# SwitchingRegulator.net
KiCad netlist of a schematic drawn in EAGLE
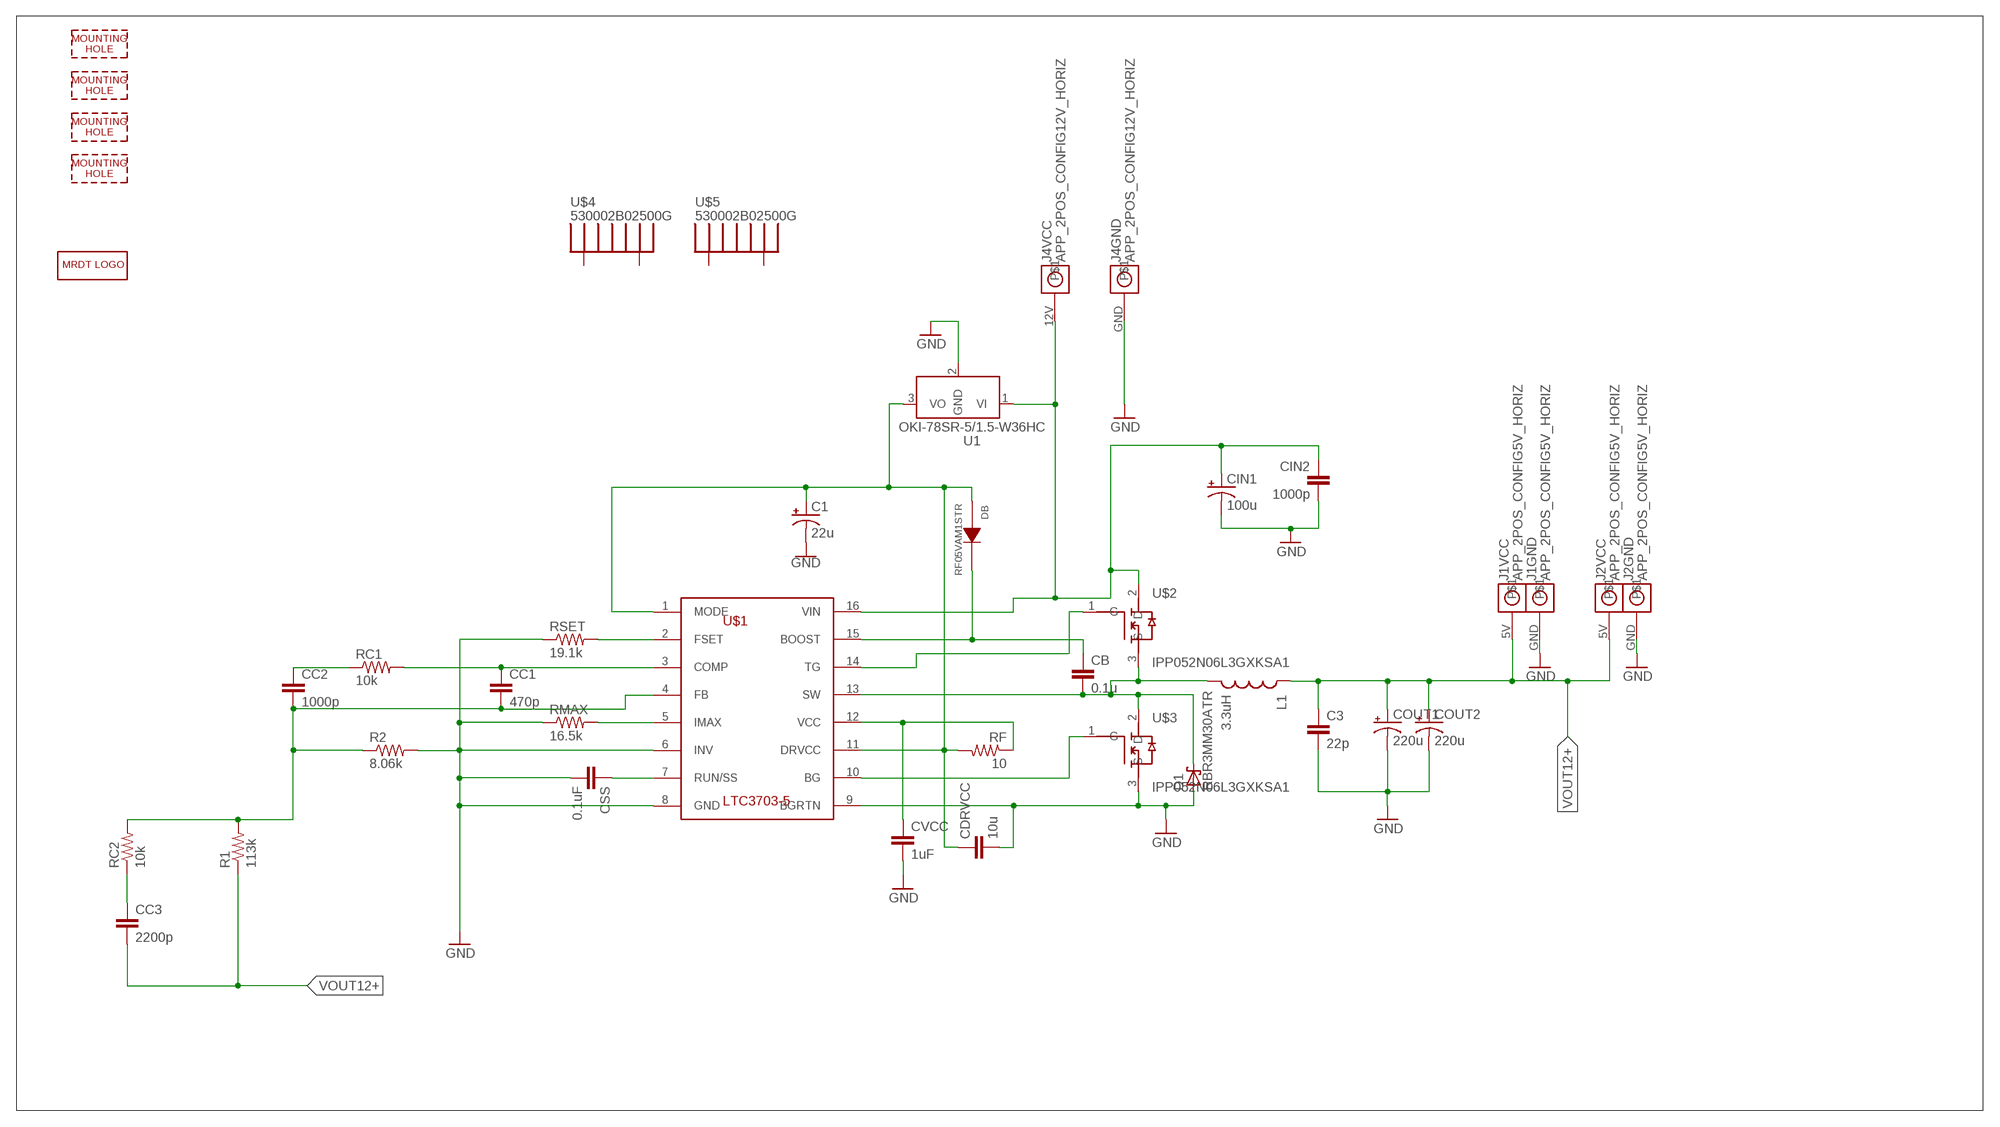
[diagram p0: schematic, sheet 1]

(export (version "E")
  (design (tool "Eeschema 10.0.6"))
  (components
    (comp (ref "C1")
      (value "22u")
      (footprint "eagle-import:CAP_POL_22UF")
      (libsource (lib "eagle-import") (part "UCZ1K220MCL1GS"))
    )
    (comp (ref "C3")
      (value "22p")
      (footprint "eagle-import:0603-CAP")
      (libsource (lib "eagle-import") (part "CAP0603-CAP"))
    )
    (comp (ref "CB")
      (value "0.1u")
      (footprint "eagle-import:0603-CAP")
      (libsource (lib "eagle-import") (part "CAP0603-CAP"))
    )
    (comp (ref "CC1")
      (value "470p")
      (footprint "eagle-import:0603-CAP")
      (libsource (lib "eagle-import") (part "CAP0603-CAP"))
    )
    (comp (ref "CC2")
      (value "1000p")
      (footprint "eagle-import:0603-CAP")
      (libsource (lib "eagle-import") (part "CAP0603-CAP"))
    )
    (comp (ref "CC3")
      (value "2200p")
      (footprint "eagle-import:0603-CAP")
      (libsource (lib "eagle-import") (part "CAP0603-CAP"))
    )
    (comp (ref "CDRVCC")
      (value "10u")
      (footprint "eagle-import:0603-CAP")
      (libsource (lib "eagle-import") (part "CAP0603-CAP"))
    )
    (comp (ref "CIN1")
      (value "100u")
      (footprint "eagle-import:CAP_POL_220UF")
      (libsource (lib "eagle-import") (part "B41858C9107M000"))
    )
    (comp (ref "CIN2")
      (value "1000p")
      (footprint "eagle-import:0603-CAP")
      (libsource (lib "eagle-import") (part "CAP0603-CAP"))
    )
    (comp (ref "COUT1")
      (value "220u")
      (footprint "eagle-import:CAP_POL_220UF")
      (libsource (lib "eagle-import") (part "EGPD101ELL221MK25H"))
    )
    (comp (ref "COUT2")
      (value "220u")
      (footprint "eagle-import:CAP_POL_220UF")
      (libsource (lib "eagle-import") (part "EGPD101ELL221MK25H"))
    )
    (comp (ref "CSS")
      (value "0.1uF")
      (footprint "eagle-import:0603-CAP")
      (libsource (lib "eagle-import") (part "CAP0603-CAP"))
    )
    (comp (ref "CVCC")
      (value "1uF")
      (footprint "eagle-import:0603-CAP")
      (libsource (lib "eagle-import") (part "CAP0603-CAP"))
    )
    (comp (ref "D1")
      (value "RBR3MM30ATR")
      (footprint "eagle-import:DIODE_SCHOTTKY_30V_1A")
      (libsource (lib "eagle-import") (part "RBR3MM30ATR"))
    )
    (comp (ref "DB")
      (value "RF05VAM1STR")
      (footprint "eagle-import:DIODE_STANDARD_100V")
      (libsource (lib "eagle-import") (part "RF05VAM1STR"))
    )
    (comp (ref "H1")
      (value "MOUNTING_HOLE#8")
      (footprint "eagle-import:#8_SCREW")
      (libsource (lib "eagle-import") (part "MOUNTING_HOLE#8"))
    )
    (comp (ref "H2")
      (value "MOUNTING_HOLE#8")
      (footprint "eagle-import:#8_SCREW")
      (libsource (lib "eagle-import") (part "MOUNTING_HOLE#8"))
    )
    (comp (ref "H3")
      (value "MOUNTING_HOLE#8")
      (footprint "eagle-import:#8_SCREW")
      (libsource (lib "eagle-import") (part "MOUNTING_HOLE#8"))
    )
    (comp (ref "H4")
      (value "MOUNTING_HOLE#8")
      (footprint "eagle-import:#8_SCREW")
      (libsource (lib "eagle-import") (part "MOUNTING_HOLE#8"))
    )
    (comp (ref "J1")
      (value "APP_2POS_CONFIG5V_HORIZ")
      (footprint "eagle-import:APP45_5V_HORIZ_CONFIG")
      (libsource (lib "eagle-import") (part "APP_2POS_CONFIG5V_HORIZ"))
    )
    (comp (ref "J2")
      (value "APP_2POS_CONFIG5V_HORIZ")
      (footprint "eagle-import:APP45_5V_HORIZ_CONFIG")
      (libsource (lib "eagle-import") (part "APP_2POS_CONFIG5V_HORIZ"))
    )
    (comp (ref "J4")
      (value "APP_2POS_CONFIG12V_HORIZ")
      (footprint "eagle-import:APP45_12V_HORIZ_CONFIG")
      (libsource (lib "eagle-import") (part "APP_2POS_CONFIG12V_HORIZ"))
    )
    (comp (ref "L1")
      (value "3.3uH")
      (footprint "eagle-import:PLANAR_INDUCTOR_3.3UH")
      (libsource (lib "eagle-import") (part "PQ3218-3R3-70-T"))
    )
    (comp (ref "LOGO1")
      (value "MRDT_LOGO")
      (footprint "eagle-import:MRDT_LOGO")
      (libsource (lib "eagle-import") (part "MRDT_LOGO"))
    )
    (comp (ref "R1")
      (value "113k")
      (footprint "eagle-import:0603-RES")
      (libsource (lib "eagle-import") (part "RESISTOR0603-RES"))
    )
    (comp (ref "R2")
      (value "8.06k")
      (footprint "eagle-import:0603-RES")
      (libsource (lib "eagle-import") (part "RESISTOR0603-RES"))
    )
    (comp (ref "RC1")
      (value "10k")
      (footprint "eagle-import:0603-RES")
      (libsource (lib "eagle-import") (part "RESISTOR0603-RES"))
    )
    (comp (ref "RC2")
      (value "10k")
      (footprint "eagle-import:0603-RES")
      (libsource (lib "eagle-import") (part "RESISTOR0603-RES"))
    )
    (comp (ref "RF")
      (value "10")
      (footprint "eagle-import:0603-RES")
      (libsource (lib "eagle-import") (part "RESISTOR0603-RES"))
    )
    (comp (ref "RMAX")
      (value "16.5k")
      (footprint "eagle-import:0603-RES")
      (libsource (lib "eagle-import") (part "RESISTOR0603-RES"))
    )
    (comp (ref "RSET")
      (value "19.1k")
      (footprint "eagle-import:0603-RES")
      (libsource (lib "eagle-import") (part "RESISTOR0603-RES"))
    )
    (comp (ref "U$1")
      (value "LTC3703-5")
      (footprint "eagle-import:SSOP-16")
      (libsource (lib "eagle-import") (part "LTC3703-5"))
    )
    (comp (ref "U$2")
      (value "IPP052N06L3GXKSA1")
      (footprint "eagle-import:TO-220")
      (libsource (lib "eagle-import") (part "IPP052N06L3GXKSA1"))
    )
    (comp (ref "U$3")
      (value "IPP052N06L3GXKSA1")
      (footprint "eagle-import:TO-220")
      (libsource (lib "eagle-import") (part "IPP052N06L3GXKSA1"))
    )
    (comp (ref "U$4")
      (value "530002B02500G")
      (footprint "eagle-import:RADIAL_FIN_HEATSINK")
      (libsource (lib "eagle-import") (part "530002B02500G"))
    )
    (comp (ref "U$5")
      (value "530002B02500G")
      (footprint "eagle-import:RADIAL_FIN_HEATSINK")
      (libsource (lib "eagle-import") (part "530002B02500G"))
    )
    (comp (ref "U1")
      (value "OKI-78SR-5/1.5-W36HC")
      (footprint "eagle-import:OKI-78SR_HORIZ")
      (libsource (lib "eagle-import") (part "OKI-78SR-/1.5-W36?CH5"))
    )
  )
  (nets
    (net (code "1") (name "GND") (class "Default")
      (node (ref "C1") (pin "-") (pinfunction "-_-") (pintype "passive"))
      (node (ref "C3") (pin "2") (pinfunction "2_2") (pintype "passive"))
      (node (ref "CDRVCC") (pin "2") (pinfunction "2_2") (pintype "passive"))
      (node (ref "CIN1") (pin "GND") (pinfunction "-_GND") (pintype "passive"))
      (node (ref "CIN2") (pin "2") (pinfunction "2_2") (pintype "passive"))
      (node (ref "COUT1") (pin "GND") (pinfunction "-_GND") (pintype "passive"))
      (node (ref "COUT2") (pin "GND") (pinfunction "-_GND") (pintype "passive"))
      (node (ref "CSS") (pin "2") (pinfunction "2_2") (pintype "passive"))
      (node (ref "CVCC") (pin "2") (pinfunction "2_2") (pintype "passive"))
      (node (ref "D1") (pin "P$1") (pinfunction "A_P$1") (pintype "passive"))
      (node (ref "J1") (pin "GND") (pinfunction "P$1_GND") (pintype "bidirectional"))
      (node (ref "J2") (pin "GND") (pinfunction "P$1_GND") (pintype "bidirectional"))
      (node (ref "J4") (pin "GND") (pinfunction "P$1_GND") (pintype "bidirectional"))
      (node (ref "R2") (pin "2") (pinfunction "2_2") (pintype "passive"))
      (node (ref "RMAX") (pin "1") (pinfunction "1_1") (pintype "passive"))
      (node (ref "RSET") (pin "1") (pinfunction "1_1") (pintype "passive"))
      (node (ref "U$1") (pin "6") (pinfunction "INV_6") (pintype "bidirectional"))
      (node (ref "U$1") (pin "8") (pinfunction "GND_8") (pintype "bidirectional"))
      (node (ref "U$1") (pin "9") (pinfunction "BGRTN_9") (pintype "bidirectional"))
      (node (ref "U$3") (pin "3") (pinfunction "S_3") (pintype "bidirectional"))
      (node (ref "U1") (pin "2") (pinfunction "GND_2") (pintype "bidirectional"))
    )
    (net (code "2") (name "Net-(CC2-Pad1)") (class "Default")
      (node (ref "CC2") (pin "1") (pinfunction "1_1") (pintype "passive"))
      (node (ref "RC1") (pin "1") (pinfunction "1_1") (pintype "passive"))
    )
    (net (code "3") (name "Net-(CC3-Pad1)") (class "Default")
      (node (ref "CC3") (pin "1") (pinfunction "1_1") (pintype "passive"))
      (node (ref "RC2") (pin "1") (pinfunction "1_1") (pintype "passive"))
    )
    (net (code "4") (name "Net-(D1-C)") (class "Default")
      (node (ref "CB") (pin "2") (pinfunction "2_2") (pintype "passive"))
      (node (ref "D1") (pin "P$2") (pinfunction "C_P$2") (pintype "passive"))
      (node (ref "L1") (pin "P$2") (pinfunction "2_P$2") (pintype "passive"))
      (node (ref "U$1") (pin "13") (pinfunction "SW_13") (pintype "bidirectional"))
      (node (ref "U$2") (pin "3") (pinfunction "S_3") (pintype "bidirectional"))
      (node (ref "U$3") (pin "2") (pinfunction "D_2") (pintype "bidirectional"))
    )
    (net (code "5") (name "Net-(DB-A)") (class "Default")
      (node (ref "C1") (pin "+") (pinfunction "+_+") (pintype "passive"))
      (node (ref "CDRVCC") (pin "1") (pinfunction "1_1") (pintype "passive"))
      (node (ref "DB") (pin "P$2") (pinfunction "A_P$2") (pintype "bidirectional"))
      (node (ref "RF") (pin "2") (pinfunction "2_2") (pintype "passive"))
      (node (ref "U$1") (pin "1") (pinfunction "MODE_1") (pintype "bidirectional"))
      (node (ref "U$1") (pin "11") (pinfunction "DRVCC_11") (pintype "bidirectional"))
      (node (ref "U1") (pin "3") (pinfunction "VO_3") (pintype "bidirectional"))
    )
    (net (code "6") (name "Net-(DB-K)") (class "Default")
      (node (ref "CB") (pin "1") (pinfunction "1_1") (pintype "passive"))
      (node (ref "DB") (pin "P$1") (pinfunction "K_P$1") (pintype "bidirectional"))
      (node (ref "U$1") (pin "15") (pinfunction "BOOST_15") (pintype "bidirectional"))
    )
    (net (code "7") (name "Net-(J4B-P$1)") (class "Default")
      (node (ref "CIN1") (pin "+") (pinfunction "+_+") (pintype "passive"))
      (node (ref "CIN2") (pin "1") (pinfunction "1_1") (pintype "passive"))
      (node (ref "J4") (pin "12V") (pinfunction "P$1_12V") (pintype "bidirectional"))
      (node (ref "U$1") (pin "16") (pinfunction "VIN_16") (pintype "bidirectional"))
      (node (ref "U$2") (pin "2") (pinfunction "D_2") (pintype "bidirectional"))
      (node (ref "U1") (pin "1") (pinfunction "VI_1") (pintype "bidirectional"))
    )
    (net (code "8") (name "Net-(U$1-BG)") (class "Default")
      (node (ref "U$1") (pin "10") (pinfunction "BG_10") (pintype "bidirectional"))
      (node (ref "U$3") (pin "1") (pinfunction "G_1") (pintype "bidirectional"))
    )
    (net (code "9") (name "Net-(U$1-COMP)") (class "Default")
      (node (ref "CC1") (pin "1") (pinfunction "1_1") (pintype "passive"))
      (node (ref "RC1") (pin "2") (pinfunction "2_2") (pintype "passive"))
      (node (ref "U$1") (pin "3") (pinfunction "COMP_3") (pintype "bidirectional"))
    )
    (net (code "10") (name "Net-(U$1-FB)") (class "Default")
      (node (ref "CC1") (pin "2") (pinfunction "2_2") (pintype "passive"))
      (node (ref "CC2") (pin "2") (pinfunction "2_2") (pintype "passive"))
      (node (ref "R1") (pin "2") (pinfunction "2_2") (pintype "passive"))
      (node (ref "R2") (pin "1") (pinfunction "1_1") (pintype "passive"))
      (node (ref "RC2") (pin "2") (pinfunction "2_2") (pintype "passive"))
      (node (ref "U$1") (pin "4") (pinfunction "FB_4") (pintype "bidirectional"))
    )
    (net (code "11") (name "Net-(U$1-FSET)") (class "Default")
      (node (ref "RSET") (pin "2") (pinfunction "2_2") (pintype "passive"))
      (node (ref "U$1") (pin "2") (pinfunction "FSET_2") (pintype "bidirectional"))
    )
    (net (code "12") (name "Net-(U$1-IMAX)") (class "Default")
      (node (ref "RMAX") (pin "2") (pinfunction "2_2") (pintype "passive"))
      (node (ref "U$1") (pin "5") (pinfunction "IMAX_5") (pintype "bidirectional"))
    )
    (net (code "13") (name "Net-(U$1-RUN{slash}SS)") (class "Default")
      (node (ref "CSS") (pin "1") (pinfunction "1_1") (pintype "passive"))
      (node (ref "U$1") (pin "7") (pinfunction "RUN/SS_7") (pintype "bidirectional"))
    )
    (net (code "14") (name "Net-(U$1-TG)") (class "Default")
      (node (ref "U$1") (pin "14") (pinfunction "TG_14") (pintype "bidirectional"))
      (node (ref "U$2") (pin "1") (pinfunction "G_1") (pintype "bidirectional"))
    )
    (net (code "15") (name "Net-(U$1-VCC)") (class "Default")
      (node (ref "CVCC") (pin "1") (pinfunction "1_1") (pintype "passive"))
      (node (ref "RF") (pin "1") (pinfunction "1_1") (pintype "passive"))
      (node (ref "U$1") (pin "12") (pinfunction "VCC_12") (pintype "bidirectional"))
    )
    (net (code "16") (name "VOUT12+") (class "Default")
      (node (ref "C3") (pin "1") (pinfunction "1_1") (pintype "passive"))
      (node (ref "CC3") (pin "2") (pinfunction "2_2") (pintype "passive"))
      (node (ref "COUT1") (pin "+") (pinfunction "+_+") (pintype "passive"))
      (node (ref "COUT2") (pin "+") (pinfunction "+_+") (pintype "passive"))
      (node (ref "J1") (pin "5V") (pinfunction "P$1_5V") (pintype "bidirectional"))
      (node (ref "J2") (pin "5V") (pinfunction "P$1_5V") (pintype "bidirectional"))
      (node (ref "L1") (pin "P$1") (pinfunction "1_P$1") (pintype "passive"))
      (node (ref "R1") (pin "1") (pinfunction "1_1") (pintype "passive"))
    )
    (net (code "17") (name "unconnected-(U$4-PadP$1)") (class "Default")
      (node (ref "U$4") (pin "P$1") (pinfunction "P$1_P$1") (pintype "bidirectional"))
    )
    (net (code "18") (name "unconnected-(U$4-PadP$2)") (class "Default")
      (node (ref "U$4") (pin "P$2") (pinfunction "P$2_P$2") (pintype "bidirectional"))
    )
    (net (code "19") (name "unconnected-(U$5-PadP$1)") (class "Default")
      (node (ref "U$5") (pin "P$1") (pinfunction "P$1_P$1") (pintype "bidirectional"))
    )
    (net (code "20") (name "unconnected-(U$5-PadP$2)") (class "Default")
      (node (ref "U$5") (pin "P$2") (pinfunction "P$2_P$2") (pintype "bidirectional"))
    )
  )
)
